# dengenver4_1.net
KiCad netlist of a schematic drawn in EAGLE
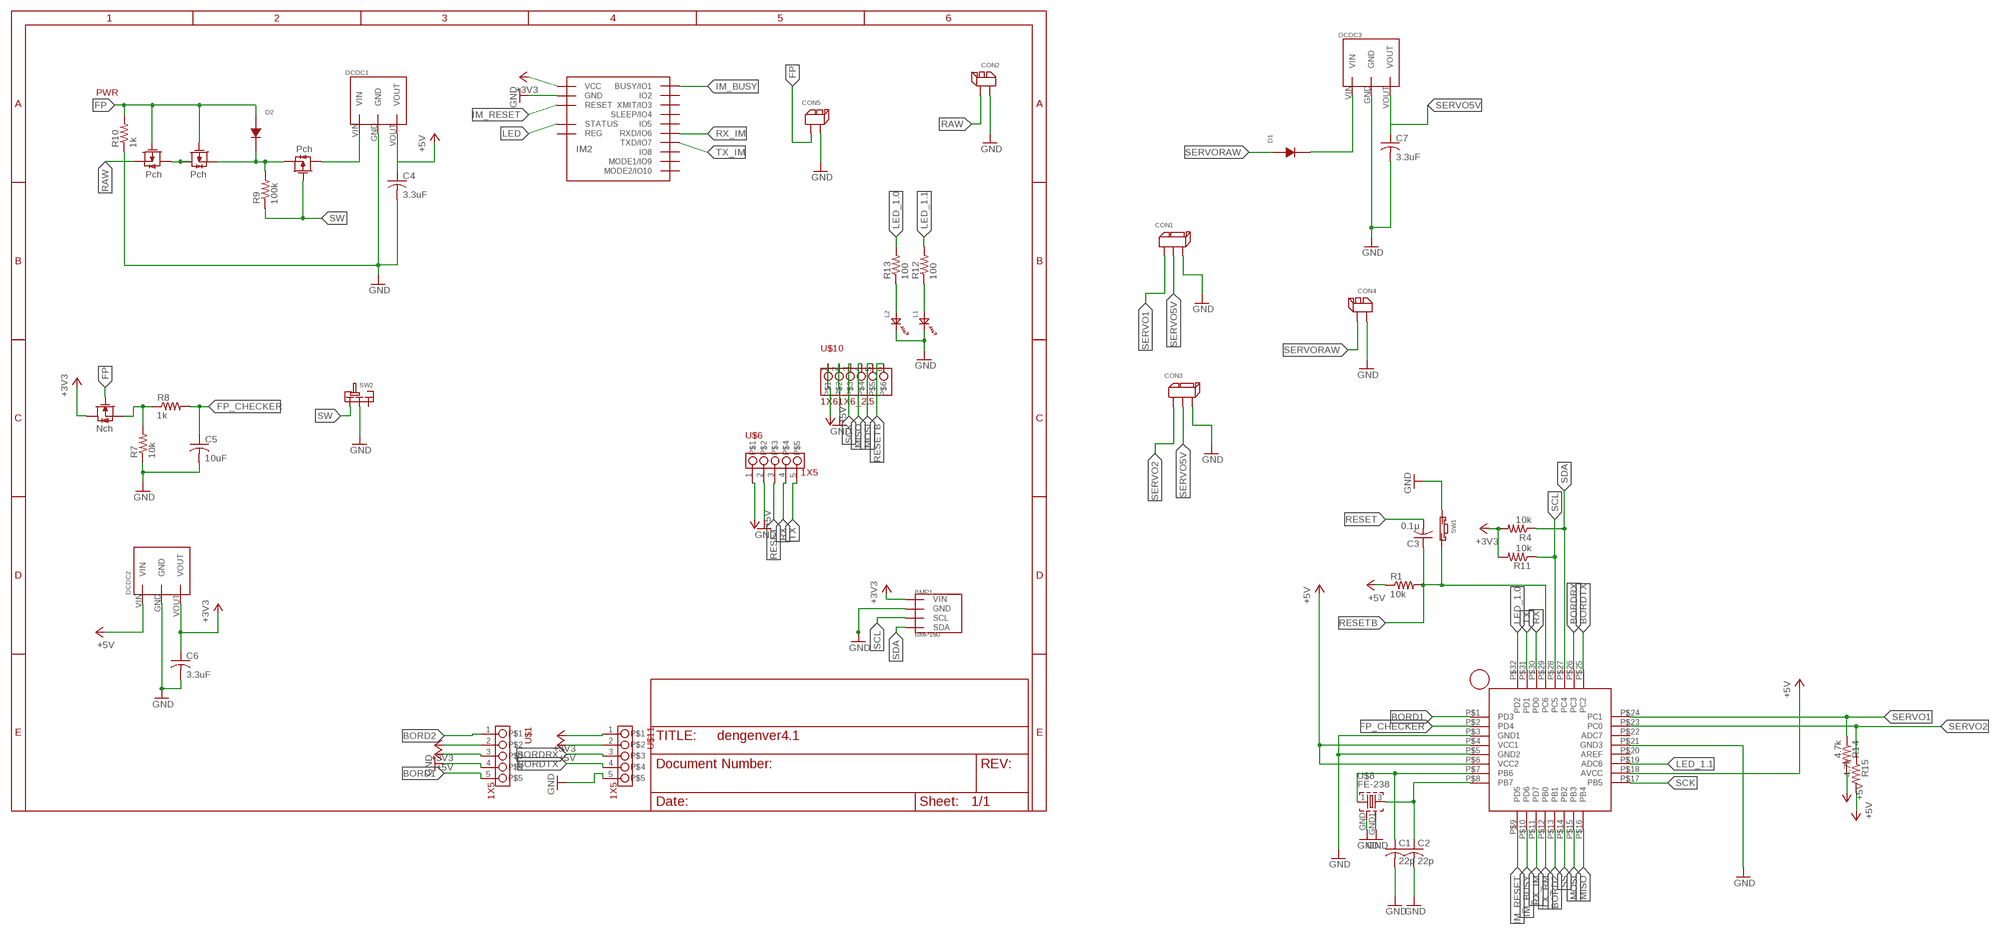
[diagram p0: schematic, sheet 1]

(export (version "E")
  (design (tool "Eeschema 10.0.6"))
  (components
    (comp (ref "BMP1")
      (value "BMP180")
      (footprint "eagle-import:GY-68")
      (libsource (lib "eagle-import") (part "BMP180"))
    )
    (comp (ref "C1")
      (value "22p")
      (footprint "eagle-import:C1608")
      (libsource (lib "eagle-import") (part "C-USC1608"))
    )
    (comp (ref "C2")
      (value "22p")
      (footprint "eagle-import:C1608")
      (libsource (lib "eagle-import") (part "C-USC1608"))
    )
    (comp (ref "C3")
      (value "0.1μ")
      (footprint "eagle-import:C1608")
      (libsource (lib "eagle-import") (part "C-USC1608"))
    )
    (comp (ref "C4")
      (value "3.3uF")
      (footprint "eagle-import:C1608")
      (libsource (lib "eagle-import") (part "C-USC1608"))
    )
    (comp (ref "C5")
      (value "10uF")
      (footprint "eagle-import:C1608")
      (libsource (lib "eagle-import") (part "C-USC1608"))
    )
    (comp (ref "C6")
      (value "3.3uF")
      (footprint "eagle-import:C1608")
      (libsource (lib "eagle-import") (part "C-USC1608"))
    )
    (comp (ref "C7")
      (value "3.3uF")
      (footprint "eagle-import:C0603")
      (libsource (lib "eagle-import") (part "C-USC0603"))
    )
    (comp (ref "CON1")
      (value "3PIN")
      (footprint "eagle-import:3PIN")
      (libsource (lib "eagle-import") (part "3PIN"))
    )
    (comp (ref "CON2")
      (value "2PIN")
      (footprint "eagle-import:2PIN")
      (libsource (lib "eagle-import") (part "2PIN"))
    )
    (comp (ref "CON3")
      (value "3PIN")
      (footprint "eagle-import:3PIN")
      (libsource (lib "eagle-import") (part "3PIN"))
    )
    (comp (ref "CON4")
      (value "2PIN")
      (footprint "eagle-import:2PIN")
      (libsource (lib "eagle-import") (part "2PIN"))
    )
    (comp (ref "CON5")
      (value "2PIN")
      (footprint "eagle-import:2PIN")
      (libsource (lib "eagle-import") (part "2PIN"))
    )
    (comp (ref "D1")
      (value "1W4148W")
      (footprint "eagle-import:SOD-123")
      (libsource (lib "eagle-import") (part "1W4148W"))
    )
    (comp (ref "D2")
      (value "1W4148W")
      (footprint "eagle-import:SOD-123")
      (libsource (lib "eagle-import") (part "1W4148W"))
    )
    (comp (ref "DCDC1")
      (value "5V1A_M78AR05-1")
      (footprint "eagle-import:5V1A_M78AR05-1")
      (libsource (lib "eagle-import") (part "5V1A_M78AR05-1"))
    )
    (comp (ref "DCDC2")
      (value "3.3V1A_M78AR033-1")
      (footprint "eagle-import:3.3V1A_M78AR033-1")
      (libsource (lib "eagle-import") (part "3.3V1A_M78AR033-1"))
    )
    (comp (ref "DCDC3")
      (value "5V1A_M78AR05-1")
      (footprint "eagle-import:5V1A_M78AR05-1")
      (libsource (lib "eagle-import") (part "5V1A_M78AR05-1"))
    )
    (comp (ref "IM2")
      (value "IM920_IM920C")
      (footprint "eagle-import:IM920_IM920C")
      (libsource (lib "eagle-import") (part "IM920_IM920C"))
    )
    (comp (ref "L1")
      (value "OSXX1608C1A")
      (footprint "eagle-import:OSXX1608C1A")
      (libsource (lib "eagle-import") (part "OSXX1608C1A"))
    )
    (comp (ref "L2")
      (value "OSXX1608C1A")
      (footprint "eagle-import:OSXX1608C1A")
      (libsource (lib "eagle-import") (part "OSXX1608C1A"))
    )
    (comp (ref "R1")
      (value "10k")
      (footprint "eagle-import:R0603")
      (libsource (lib "eagle-import") (part "R-US_R0603"))
    )
    (comp (ref "R4")
      (value "10k")
      (footprint "eagle-import:R0603")
      (libsource (lib "eagle-import") (part "R-US_R0603"))
    )
    (comp (ref "R7")
      (value "10k")
      (footprint "eagle-import:R0603")
      (libsource (lib "eagle-import") (part "R-US_R0603"))
    )
    (comp (ref "R8")
      (value "1k")
      (footprint "eagle-import:R0603")
      (libsource (lib "eagle-import") (part "R-US_R0603"))
    )
    (comp (ref "R9")
      (value "100k")
      (footprint "eagle-import:R0603")
      (libsource (lib "eagle-import") (part "R-US_R0603"))
    )
    (comp (ref "R10")
      (value "1k")
      (footprint "eagle-import:R0603")
      (libsource (lib "eagle-import") (part "R-US_R0603"))
    )
    (comp (ref "R11")
      (value "10k")
      (footprint "eagle-import:R0603")
      (libsource (lib "eagle-import") (part "R-US_R0603"))
    )
    (comp (ref "R12")
      (value "100")
      (footprint "eagle-import:R0603")
      (libsource (lib "eagle-import") (part "R-US_R0603"))
    )
    (comp (ref "R13")
      (value "100")
      (footprint "eagle-import:R0603")
      (libsource (lib "eagle-import") (part "R-US_R0603"))
    )
    (comp (ref "R14")
      (value "4.7k")
      (footprint "eagle-import:R0603")
      (libsource (lib "eagle-import") (part "R-US_R0603"))
    )
    (comp (ref "R15")
      (value "4.7k")
      (footprint "eagle-import:R0603")
      (libsource (lib "eagle-import") (part "R-US_R0603"))
    )
    (comp (ref "SW1")
      (value "TVAF06-A020B-R")
      (footprint "eagle-import:TVAF06-A020B-R")
      (libsource (lib "eagle-import") (part "TVAF06-A020B-R"))
    )
    (comp (ref "SW2")
      (value "SRIDE_SWITCH")
      (footprint "eagle-import:SRIDE_SWITCH")
      (libsource (lib "eagle-import") (part "SRIDE_SWITCH"))
    )
    (comp (ref "U$1")
      (value "1X5")
      (footprint "eagle-import:HDRVR5W64P254_1X5_1310X250X865B")
      (libsource (lib "eagle-import") (part "1X5"))
    )
    (comp (ref "U$2")
      (value "2SJ681-PCH")
      (footprint "eagle-import:2SJ681")
      (libsource (lib "eagle-import") (part "2SJ681-PCH"))
    )
    (comp (ref "U$3")
      (value "2SK4017-NCH")
      (footprint "eagle-import:2SK4017")
      (libsource (lib "eagle-import") (part "2SK4017-NCH"))
    )
    (comp (ref "U$4")
      (value "2SJ681-PCH")
      (footprint "eagle-import:2SJ681")
      (libsource (lib "eagle-import") (part "2SJ681-PCH"))
    )
    (comp (ref "U$5")
      (value "2SJ681-PCH")
      (footprint "eagle-import:2SJ681")
      (libsource (lib "eagle-import") (part "2SJ681-PCH"))
    )
    (comp (ref "U$6")
      (value "1X5")
      (footprint "eagle-import:HDRVR5W64P254_1X5_1310X250X865B")
      (libsource (lib "eagle-import") (part "1X5"))
    )
    (comp (ref "U$7")
      (value "ATMEGA328P-AUATMEGA328P-AU")
      (footprint "eagle-import:ATMEGA328P-AU")
      (libsource (lib "eagle-import") (part "ATMEGA328P-AUATMEGA328P-AU"))
    )
    (comp (ref "U$8")
      (value "FE-238")
      (footprint "eagle-import:OSCCC300X230X120N")
      (libsource (lib "eagle-import") (part "FE-238"))
    )
    (comp (ref "U$10")
      (value "1X61X6_2.5")
      (footprint "eagle-import:HDRVR6W64P254_1X6_1564X250X865B")
      (libsource (lib "eagle-import") (part "1X61X6_2.5"))
    )
    (comp (ref "U$11")
      (value "1X5")
      (footprint "eagle-import:HDRVR5W64P254_1X5_1310X250X865B")
      (libsource (lib "eagle-import") (part "1X5"))
    )
  )
  (nets
    (net (code "1") (name "+3V3") (class "Default")
      (node (ref "BMP1") (pin "P1") (pinfunction "VIN_P1") (pintype "bidirectional"))
      (node (ref "C6") (pin "1") (pinfunction "1_1") (pintype "passive"))
      (node (ref "DCDC2") (pin "VOUT") (pinfunction "VOUT_VOUT") (pintype "bidirectional"))
      (node (ref "IM2") (pin "$P17") (pinfunction "VCC_$P17") (pintype "bidirectional"))
      (node (ref "R11") (pin "2") (pinfunction "2_2") (pintype "passive"))
      (node (ref "R4") (pin "2") (pinfunction "2_2") (pintype "passive"))
      (node (ref "U$1") (pin "2") (pinfunction "P$2_2") (pintype "bidirectional"))
      (node (ref "U$11") (pin "1") (pinfunction "P$1_1") (pintype "bidirectional"))
      (node (ref "U$3") (pin "DRAIN") (pinfunction "DRAIN_DRAIN") (pintype "bidirectional"))
    )
    (net (code "2") (name "+5V") (class "Default")
      (node (ref "C4") (pin "1") (pinfunction "1_1") (pintype "passive"))
      (node (ref "DCDC1") (pin "VOUT") (pinfunction "VOUT_VOUT") (pintype "bidirectional"))
      (node (ref "DCDC2") (pin "VIN") (pinfunction "VIN_VIN") (pintype "bidirectional"))
      (node (ref "R1") (pin "1") (pinfunction "1_1") (pintype "passive"))
      (node (ref "R14") (pin "2") (pinfunction "2_2") (pintype "passive"))
      (node (ref "R15") (pin "2") (pinfunction "2_2") (pintype "passive"))
      (node (ref "U$1") (pin "3") (pinfunction "P$3_3") (pintype "bidirectional"))
      (node (ref "U$10") (pin "1") (pinfunction "P$1_1") (pintype "bidirectional"))
      (node (ref "U$11") (pin "2") (pinfunction "P$2_2") (pintype "bidirectional"))
      (node (ref "U$6") (pin "1") (pinfunction "P$1_1") (pintype "bidirectional"))
      (node (ref "U$7") (pin "P$18") (pinfunction "AVCC_P$18") (pintype "bidirectional"))
      (node (ref "U$7") (pin "P$4") (pinfunction "VCC1_P$4") (pintype "bidirectional"))
      (node (ref "U$7") (pin "P$6") (pinfunction "VCC2_P$6") (pintype "bidirectional"))
    )
    (net (code "3") (name "BORD1") (class "Default")
      (node (ref "U$1") (pin "5") (pinfunction "P$5_5") (pintype "bidirectional"))
      (node (ref "U$7") (pin "P$1") (pinfunction "PD3_P$1") (pintype "bidirectional"))
    )
    (net (code "4") (name "BORD2") (class "Default")
      (node (ref "U$1") (pin "1") (pinfunction "P$1_1") (pintype "bidirectional"))
      (node (ref "U$7") (pin "P$13") (pinfunction "PB1_P$13") (pintype "bidirectional"))
    )
    (net (code "5") (name "BORDRX") (class "Default")
      (node (ref "U$11") (pin "3") (pinfunction "P$3_3") (pintype "bidirectional"))
      (node (ref "U$7") (pin "P$26") (pinfunction "PC3_P$26") (pintype "bidirectional"))
    )
    (net (code "6") (name "BORDTX") (class "Default")
      (node (ref "U$11") (pin "4") (pinfunction "P$4_4") (pintype "bidirectional"))
      (node (ref "U$7") (pin "P$25") (pinfunction "PC2_P$25") (pintype "bidirectional"))
    )
    (net (code "7") (name "FP") (class "Default")
      (node (ref "CON5") (pin "P$1") (pinfunction "P$1_P$1") (pintype "bidirectional"))
      (node (ref "D2") (pin "C") (pinfunction "C_C") (pintype "bidirectional"))
      (node (ref "R10") (pin "2") (pinfunction "2_2") (pintype "passive"))
      (node (ref "U$2") (pin "GATE") (pinfunction "GATE_GATE") (pintype "bidirectional"))
      (node (ref "U$3") (pin "GATE") (pinfunction "GATE_GATE") (pintype "bidirectional"))
      (node (ref "U$4") (pin "GATE") (pinfunction "GATE_GATE") (pintype "bidirectional"))
    )
    (net (code "8") (name "FP_CHECKER") (class "Default")
      (node (ref "C5") (pin "1") (pinfunction "1_1") (pintype "passive"))
      (node (ref "R8") (pin "2") (pinfunction "2_2") (pintype "passive"))
      (node (ref "U$7") (pin "P$2") (pinfunction "PD4_P$2") (pintype "bidirectional"))
    )
    (net (code "9") (name "GND") (class "Default")
      (node (ref "BMP1") (pin "P2") (pinfunction "GND_P2") (pintype "bidirectional"))
      (node (ref "C1") (pin "2") (pinfunction "2_2") (pintype "passive"))
      (node (ref "C2") (pin "2") (pinfunction "2_2") (pintype "passive"))
      (node (ref "C4") (pin "2") (pinfunction "2_2") (pintype "passive"))
      (node (ref "C5") (pin "2") (pinfunction "2_2") (pintype "passive"))
      (node (ref "C6") (pin "2") (pinfunction "2_2") (pintype "passive"))
      (node (ref "C7") (pin "2") (pinfunction "2_2") (pintype "passive"))
      (node (ref "CON1") (pin "P$3") (pinfunction "P$3_P$3") (pintype "bidirectional"))
      (node (ref "CON2") (pin "P$1") (pinfunction "P$1_P$1") (pintype "bidirectional"))
      (node (ref "CON3") (pin "P$3") (pinfunction "P$3_P$3") (pintype "bidirectional"))
      (node (ref "CON4") (pin "P$1") (pinfunction "P$1_P$1") (pintype "bidirectional"))
      (node (ref "CON5") (pin "P$2") (pinfunction "P$2_P$2") (pintype "bidirectional"))
      (node (ref "DCDC1") (pin "GND") (pinfunction "GND_GND") (pintype "bidirectional"))
      (node (ref "DCDC2") (pin "GND") (pinfunction "GND_GND") (pintype "bidirectional"))
      (node (ref "DCDC3") (pin "GND") (pinfunction "GND_GND") (pintype "bidirectional"))
      (node (ref "IM2") (pin "$P18") (pinfunction "GND_$P18") (pintype "bidirectional"))
      (node (ref "L1") (pin "CT") (pinfunction "CT_CT") (pintype "bidirectional"))
      (node (ref "L2") (pin "CT") (pinfunction "CT_CT") (pintype "bidirectional"))
      (node (ref "R10") (pin "1") (pinfunction "1_1") (pintype "passive"))
      (node (ref "R7") (pin "1") (pinfunction "1_1") (pintype "passive"))
      (node (ref "SW1") (pin "P$1") (pinfunction "P$1_P$1") (pintype "bidirectional"))
      (node (ref "SW2") (pin "LR") (pinfunction "LR_LR") (pintype "bidirectional"))
      (node (ref "U$1") (pin "4") (pinfunction "P$4_4") (pintype "bidirectional"))
      (node (ref "U$10") (pin "2") (pinfunction "P$2_2") (pintype "bidirectional"))
      (node (ref "U$11") (pin "5") (pinfunction "P$5_5") (pintype "bidirectional"))
      (node (ref "U$6") (pin "2") (pinfunction "P$2_2") (pintype "bidirectional"))
      (node (ref "U$7") (pin "P$21") (pinfunction "GND3_P$21") (pintype "bidirectional"))
      (node (ref "U$7") (pin "P$3") (pinfunction "GND1_P$3") (pintype "bidirectional"))
      (node (ref "U$7") (pin "P$5") (pinfunction "GND2_P$5") (pintype "bidirectional"))
      (node (ref "U$8") (pin "GND") (pinfunction "GND_GND") (pintype "passive"))
      (node (ref "U$8") (pin "GND1") (pinfunction "GND1_GND1") (pintype "passive"))
    )
    (net (code "10") (name "IM_BUSY") (class "Default")
      (node (ref "IM2") (pin "$P1") (pinfunction "BUSY/IO1_$P1") (pintype "bidirectional"))
      (node (ref "U$7") (pin "P$10") (pinfunction "PD6_P$10") (pintype "bidirectional"))
    )
    (net (code "11") (name "IM_RESET") (class "Default")
      (node (ref "IM2") (pin "$P19") (pinfunction "RESET_$P19") (pintype "bidirectional"))
      (node (ref "U$7") (pin "P$9") (pinfunction "PD5_P$9") (pintype "bidirectional"))
    )
    (net (code "12") (name "LED") (class "Default")
      (node (ref "IM2") (pin "$P15") (pinfunction "STATUS_$P15") (pintype "bidirectional"))
    )
    (net (code "13") (name "LED_1.0") (class "Default")
      (node (ref "R13") (pin "2") (pinfunction "2_2") (pintype "passive"))
      (node (ref "U$7") (pin "P$32") (pinfunction "PD2_P$32") (pintype "bidirectional"))
    )
    (net (code "14") (name "LED_1.1") (class "Default")
      (node (ref "R12") (pin "2") (pinfunction "2_2") (pintype "passive"))
      (node (ref "U$7") (pin "P$19") (pinfunction "ADC6_P$19") (pintype "bidirectional"))
    )
    (net (code "15") (name "MISO") (class "Default")
      (node (ref "U$10") (pin "4") (pinfunction "P$4_4") (pintype "bidirectional"))
      (node (ref "U$7") (pin "P$16") (pinfunction "PB4_P$16") (pintype "bidirectional"))
    )
    (net (code "16") (name "MOSI") (class "Default")
      (node (ref "U$10") (pin "5") (pinfunction "P$5_5") (pintype "bidirectional"))
      (node (ref "U$7") (pin "P$15") (pinfunction "PB3_P$15") (pintype "bidirectional"))
    )
    (net (code "17") (name "Net-(D2-PadA)") (class "Default")
      (node (ref "D2") (pin "A") (pinfunction "A_A") (pintype "bidirectional"))
      (node (ref "R9") (pin "2") (pinfunction "2_2") (pintype "passive"))
      (node (ref "U$4") (pin "SOURCE") (pinfunction "SOURCE_SOURCE") (pintype "bidirectional"))
      (node (ref "U$5") (pin "SOURCE") (pinfunction "SOURCE_SOURCE") (pintype "bidirectional"))
    )
    (net (code "18") (name "Net-(DCDC1-PadVIN)") (class "Default")
      (node (ref "DCDC1") (pin "VIN") (pinfunction "VIN_VIN") (pintype "bidirectional"))
      (node (ref "U$5") (pin "DRAIN") (pinfunction "DRAIN_DRAIN") (pintype "bidirectional"))
    )
    (net (code "19") (name "Net-(L1-PadAN)") (class "Default")
      (node (ref "L1") (pin "AN") (pinfunction "AN_AN") (pintype "bidirectional"))
      (node (ref "R12") (pin "1") (pinfunction "1_1") (pintype "passive"))
    )
    (net (code "20") (name "Net-(L2-PadAN)") (class "Default")
      (node (ref "L2") (pin "AN") (pinfunction "AN_AN") (pintype "bidirectional"))
      (node (ref "R13") (pin "1") (pinfunction "1_1") (pintype "passive"))
    )
    (net (code "21") (name "Net-(R7-Pad2)") (class "Default")
      (node (ref "R7") (pin "2") (pinfunction "2_2") (pintype "passive"))
      (node (ref "R8") (pin "1") (pinfunction "1_1") (pintype "passive"))
      (node (ref "U$3") (pin "SOURCE") (pinfunction "SOURCE_SOURCE") (pintype "bidirectional"))
    )
    (net (code "22") (name "Net-(U$2-PadDRAIN)") (class "Default")
      (node (ref "U$2") (pin "DRAIN") (pinfunction "DRAIN_DRAIN") (pintype "bidirectional"))
      (node (ref "U$4") (pin "DRAIN") (pinfunction "DRAIN_DRAIN") (pintype "bidirectional"))
    )
    (net (code "23") (name "Net-(U$7-PB6)") (class "Default")
      (node (ref "C1") (pin "1") (pinfunction "1_1") (pintype "passive"))
      (node (ref "U$7") (pin "P$7") (pinfunction "PB6_P$7") (pintype "bidirectional"))
      (node (ref "U$8") (pin "1") (pinfunction "1_1") (pintype "passive"))
    )
    (net (code "24") (name "Net-(U$7-PB7)") (class "Default")
      (node (ref "C2") (pin "1") (pinfunction "1_1") (pintype "passive"))
      (node (ref "U$7") (pin "P$8") (pinfunction "PB7_P$8") (pintype "bidirectional"))
      (node (ref "U$8") (pin "3") (pinfunction "3_3") (pintype "passive"))
    )
    (net (code "25") (name "RAW") (class "Default")
      (node (ref "CON2") (pin "P$2") (pinfunction "P$2_P$2") (pintype "bidirectional"))
      (node (ref "U$2") (pin "SOURCE") (pinfunction "SOURCE_SOURCE") (pintype "bidirectional"))
    )
    (net (code "26") (name "RESET") (class "Default")
      (node (ref "C3") (pin "2") (pinfunction "2_2") (pintype "passive"))
      (node (ref "U$6") (pin "3") (pinfunction "P$3_3") (pintype "bidirectional"))
    )
    (net (code "27") (name "RESETB") (class "Default")
      (node (ref "C3") (pin "1") (pinfunction "1_1") (pintype "passive"))
      (node (ref "R1") (pin "2") (pinfunction "2_2") (pintype "passive"))
      (node (ref "SW1") (pin "P$2") (pinfunction "P$2_P$2") (pintype "bidirectional"))
      (node (ref "U$10") (pin "6") (pinfunction "P$6_6") (pintype "bidirectional"))
      (node (ref "U$7") (pin "P$29") (pinfunction "PC6_P$29") (pintype "bidirectional"))
    )
    (net (code "28") (name "RX") (class "Default")
      (node (ref "U$6") (pin "4") (pinfunction "P$4_4") (pintype "bidirectional"))
      (node (ref "U$7") (pin "P$30") (pinfunction "PD0_P$30") (pintype "bidirectional"))
    )
    (net (code "29") (name "RX_IM") (class "Default")
      (node (ref "IM2") (pin "$P6") (pinfunction "RXD/IO6_$P6") (pintype "bidirectional"))
      (node (ref "U$7") (pin "P$11") (pinfunction "PD7_P$11") (pintype "bidirectional"))
    )
    (net (code "30") (name "SCK") (class "Default")
      (node (ref "U$10") (pin "3") (pinfunction "P$3_3") (pintype "bidirectional"))
      (node (ref "U$7") (pin "P$17") (pinfunction "PB5_P$17") (pintype "bidirectional"))
    )
    (net (code "31") (name "SCL") (class "Default")
      (node (ref "BMP1") (pin "P3") (pinfunction "SCL_P3") (pintype "bidirectional"))
      (node (ref "R11") (pin "1") (pinfunction "1_1") (pintype "passive"))
      (node (ref "U$7") (pin "P$28") (pinfunction "PC5_P$28") (pintype "bidirectional"))
    )
    (net (code "32") (name "SDA") (class "Default")
      (node (ref "BMP1") (pin "P4") (pinfunction "SDA_P4") (pintype "bidirectional"))
      (node (ref "R4") (pin "1") (pinfunction "1_1") (pintype "passive"))
      (node (ref "U$7") (pin "P$27") (pinfunction "PC4_P$27") (pintype "bidirectional"))
    )
    (net (code "33") (name "SERVO1") (class "Default")
      (node (ref "CON1") (pin "P$1") (pinfunction "P$1_P$1") (pintype "bidirectional"))
      (node (ref "R14") (pin "1") (pinfunction "1_1") (pintype "passive"))
      (node (ref "U$7") (pin "P$24") (pinfunction "PC1_P$24") (pintype "bidirectional"))
    )
    (net (code "34") (name "SERVO2") (class "Default")
      (node (ref "CON3") (pin "P$1") (pinfunction "P$1_P$1") (pintype "bidirectional"))
      (node (ref "R15") (pin "1") (pinfunction "1_1") (pintype "passive"))
      (node (ref "U$7") (pin "P$23") (pinfunction "PC0_P$23") (pintype "bidirectional"))
    )
    (net (code "35") (name "SERVO5V") (class "Default")
      (node (ref "C7") (pin "1") (pinfunction "1_1") (pintype "passive"))
      (node (ref "CON1") (pin "P$2") (pinfunction "P$2_P$2") (pintype "bidirectional"))
      (node (ref "CON3") (pin "P$2") (pinfunction "P$2_P$2") (pintype "bidirectional"))
      (node (ref "DCDC3") (pin "VOUT") (pinfunction "VOUT_VOUT") (pintype "bidirectional"))
    )
    (net (code "36") (name "SERVORAW") (class "Default")
      (node (ref "CON4") (pin "P$2") (pinfunction "P$2_P$2") (pintype "bidirectional"))
      (node (ref "D1") (pin "A") (pinfunction "A_A") (pintype "bidirectional"))
      (node (ref "DCDC3") (pin "VIN") (pinfunction "VIN_VIN") (pintype "bidirectional"))
    )
    (net (code "37") (name "SS") (class "Default")
      (node (ref "U$7") (pin "P$14") (pinfunction "PB2_P$14") (pintype "bidirectional"))
    )
    (net (code "38") (name "SW") (class "Default")
      (node (ref "R9") (pin "1") (pinfunction "1_1") (pintype "passive"))
      (node (ref "SW2") (pin "L") (pinfunction "L_L") (pintype "bidirectional"))
      (node (ref "U$5") (pin "GATE") (pinfunction "GATE_GATE") (pintype "bidirectional"))
    )
    (net (code "39") (name "TX") (class "Default")
      (node (ref "U$6") (pin "5") (pinfunction "P$5_5") (pintype "bidirectional"))
      (node (ref "U$7") (pin "P$31") (pinfunction "PD1_P$31") (pintype "bidirectional"))
    )
    (net (code "40") (name "TX_IM") (class "Default")
      (node (ref "IM2") (pin "$P7") (pinfunction "TXD/IO7_$P7") (pintype "bidirectional"))
    )
    (net (code "41") (name "TX_RM") (class "Default")
      (node (ref "U$7") (pin "P$12") (pinfunction "PB0_P$12") (pintype "bidirectional"))
    )
    (net (code "42") (name "unconnected-(D1-PadC)") (class "Default")
      (node (ref "D1") (pin "C") (pinfunction "C_C") (pintype "bidirectional"))
    )
    (net (code "43") (name "unconnected-(IM2-IO2-Pad$P2)") (class "Default")
      (node (ref "IM2") (pin "$P2") (pinfunction "IO2_$P2") (pintype "bidirectional"))
    )
    (net (code "44") (name "unconnected-(IM2-IO5-Pad$P5)") (class "Default")
      (node (ref "IM2") (pin "$P5") (pinfunction "IO5_$P5") (pintype "bidirectional"))
    )
    (net (code "45") (name "unconnected-(IM2-IO8-Pad$P8)") (class "Default")
      (node (ref "IM2") (pin "$P8") (pinfunction "IO8_$P8") (pintype "bidirectional"))
    )
    (net (code "46") (name "unconnected-(IM2-MODE1{slash}IO9-Pad$P9)") (class "Default")
      (node (ref "IM2") (pin "$P9") (pinfunction "MODE1/IO9_$P9") (pintype "bidirectional"))
    )
    (net (code "47") (name "unconnected-(IM2-MODE2{slash}IO10-Pad$P10)") (class "Default")
      (node (ref "IM2") (pin "$P10") (pinfunction "MODE2/IO10_$P10") (pintype "bidirectional"))
    )
    (net (code "48") (name "unconnected-(IM2-REG-Pad$P16)") (class "Default")
      (node (ref "IM2") (pin "$P16") (pinfunction "REG_$P16") (pintype "bidirectional"))
    )
    (net (code "49") (name "unconnected-(IM2-SLEEP{slash}IO4-Pad$P4)") (class "Default")
      (node (ref "IM2") (pin "$P4") (pinfunction "SLEEP/IO4_$P4") (pintype "bidirectional"))
    )
    (net (code "50") (name "unconnected-(IM2-XMIT{slash}IO3-Pad$P3)") (class "Default")
      (node (ref "IM2") (pin "$P3") (pinfunction "XMIT/IO3_$P3") (pintype "bidirectional"))
    )
    (net (code "51") (name "unconnected-(SW2-PadR)") (class "Default")
      (node (ref "SW2") (pin "R") (pinfunction "R_R") (pintype "bidirectional"))
    )
    (net (code "52") (name "unconnected-(U$7-ADC7-PadP$22)") (class "Default")
      (node (ref "U$7") (pin "P$22") (pinfunction "ADC7_P$22") (pintype "bidirectional"))
    )
    (net (code "53") (name "unconnected-(U$7-AREF-PadP$20)") (class "Default")
      (node (ref "U$7") (pin "P$20") (pinfunction "AREF_P$20") (pintype "bidirectional"))
    )
  )
)
